# ArduinoShield.net
KiCad netlist of a schematic drawn in Altium Designer
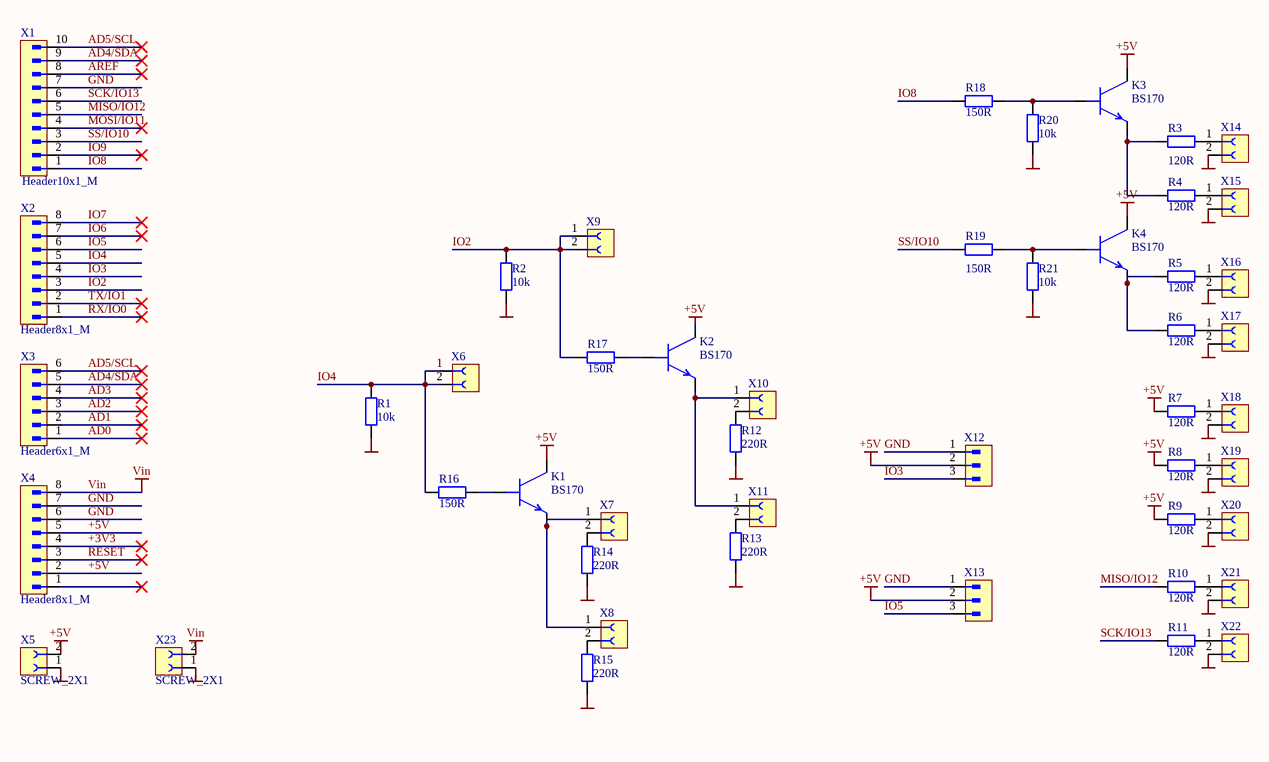
[diagram p0: ArduinoShield.SchDoc]

(export (version "E")
  (design (tool "Eeschema 10.0.6"))
  (components
    (comp (ref "K1")
      (value "BS170")
      (footprint "TO-92")
      (description "Small Signal Bipolar Transistor, 0.1A I(C), 65V V(BR)CEO, 1-Element, NPN, Silicon, TO-92")
      (fields (field (name "POWER") "625mW"))
      (libsource (lib "CPNV Centre professionnel du Nord vaudois") (part "Bipolar NPN"))
    )
    (comp (ref "K2")
      (value "BS170")
      (footprint "TO-92")
      (description "Small Signal Bipolar Transistor, 0.1A I(C), 65V V(BR)CEO, 1-Element, NPN, Silicon, TO-92")
      (fields (field (name "POWER") "625mW"))
      (libsource (lib "CPNV Centre professionnel du Nord vaudois") (part "Bipolar NPN"))
    )
    (comp (ref "K3")
      (value "BS170")
      (footprint "TO-92")
      (description "Small Signal Bipolar Transistor, 0.1A I(C), 65V V(BR)CEO, 1-Element, NPN, Silicon, TO-92")
      (fields (field (name "POWER") "625mW"))
      (libsource (lib "CPNV Centre professionnel du Nord vaudois") (part "Bipolar NPN"))
    )
    (comp (ref "K4")
      (value "BS170")
      (footprint "TO-92")
      (description "Small Signal Bipolar Transistor, 0.1A I(C), 65V V(BR)CEO, 1-Element, NPN, Silicon, TO-92")
      (fields (field (name "POWER") "625mW"))
      (libsource (lib "CPNV Centre professionnel du Nord vaudois") (part "Bipolar NPN"))
    )
    (comp (ref "R1")
      (value "10k")
      (footprint "AXIAL-1/2W")
      (description "Resistor")
      (libsource (lib "Passif_et_Semi-conducteurs") (part "RES"))
    )
    (comp (ref "R2")
      (value "10k")
      (footprint "AXIAL-1/2W")
      (description "Resistor")
      (libsource (lib "Passif_et_Semi-conducteurs") (part "RES"))
    )
    (comp (ref "R3")
      (value "120R")
      (footprint "AXIAL-1/2W")
      (description "Resistor")
      (libsource (lib "") (part "RES_1"))
    )
    (comp (ref "R4")
      (value "120R")
      (footprint "AXIAL-1/2W")
      (description "Resistor")
      (libsource (lib "") (part "RES_1"))
    )
    (comp (ref "R5")
      (value "120R")
      (footprint "AXIAL-1/2W")
      (description "Resistor")
      (libsource (lib "") (part "RES_1"))
    )
    (comp (ref "R6")
      (value "120R")
      (footprint "AXIAL-1/2W")
      (description "Resistor")
      (libsource (lib "") (part "RES_1"))
    )
    (comp (ref "R7")
      (value "120R")
      (footprint "AXIAL-1/2W")
      (description "Resistor")
      (libsource (lib "") (part "RES_1"))
    )
    (comp (ref "R8")
      (value "120R")
      (footprint "AXIAL-1/2W")
      (description "Resistor")
      (libsource (lib "") (part "RES_1"))
    )
    (comp (ref "R9")
      (value "120R")
      (footprint "AXIAL-1/2W")
      (description "Resistor")
      (libsource (lib "") (part "RES_1"))
    )
    (comp (ref "R10")
      (value "120R")
      (footprint "AXIAL-1/2W")
      (description "Resistor")
      (libsource (lib "") (part "RES_1"))
    )
    (comp (ref "R11")
      (value "120R")
      (footprint "AXIAL-1/2W")
      (description "Resistor")
      (libsource (lib "") (part "RES_1"))
    )
    (comp (ref "R12")
      (value "220R")
      (footprint "AXIAL-1/2W")
      (description "Resistor")
      (libsource (lib "Passif_et_Semi-conducteurs") (part "RES"))
    )
    (comp (ref "R13")
      (value "220R")
      (footprint "AXIAL-1/2W")
      (description "Resistor")
      (libsource (lib "Passif_et_Semi-conducteurs") (part "RES"))
    )
    (comp (ref "R14")
      (value "220R")
      (footprint "AXIAL-1/2W")
      (description "Resistor")
      (libsource (lib "Passif_et_Semi-conducteurs") (part "RES"))
    )
    (comp (ref "R15")
      (value "220R")
      (footprint "AXIAL-1/2W")
      (description "Resistor")
      (libsource (lib "Passif_et_Semi-conducteurs") (part "RES"))
    )
    (comp (ref "R16")
      (value "150R")
      (footprint "AXIAL-1/2W")
      (description "Resistor")
      (libsource (lib "") (part "RES_1"))
    )
    (comp (ref "R17")
      (value "150R")
      (footprint "AXIAL-1/2W")
      (description "Resistor")
      (libsource (lib "") (part "RES_1"))
    )
    (comp (ref "R18")
      (value "150R")
      (footprint "AXIAL-1/2W")
      (description "Resistor")
      (libsource (lib "") (part "RES_1"))
    )
    (comp (ref "R19")
      (value "150R")
      (footprint "AXIAL-1/2W")
      (description "Resistor")
      (libsource (lib "") (part "RES_1"))
    )
    (comp (ref "R20")
      (value "10k")
      (footprint "AXIAL-1/2W")
      (description "Resistor")
      (libsource (lib "Passif_et_Semi-conducteurs") (part "RES"))
    )
    (comp (ref "R21")
      (value "10k")
      (footprint "AXIAL-1/2W")
      (description "Resistor")
      (libsource (lib "Passif_et_Semi-conducteurs") (part "RES"))
    )
    (comp (ref "X1")
      (value "Header10x1_M")
      (footprint "HDR10X1_M")
      (fields
        (field (name "MANUFACTURER PART NUMBER") "61301011121")
        (field (name "MANUFACTURER") "Wurth Electronics")
        (field (name "SOURCE") "MEION_Connectors.SchLib")
      )
      (libsource (lib "CPNV Centre professionnel du Nord vaudois") (part "Header10x1_M"))
    )
    (comp (ref "X2")
      (value "Header8x1_M")
      (footprint "HDR8X1_M")
      (description "Board-To-Board Connector, Vertical, Wr-Phd Series, Through Hole, Header, 8, 2.54 Mm")
      (fields
        (field (name "MANUFACTURER") "Wurth Electronics")
        (field (name "MANUFACTURER PART NUMBER") "61300811121")
        (field (name "SOURCE") "MEION_Connectors.SchLib")
      )
      (libsource (lib "CPNV Centre professionnel du Nord vaudois") (part "Header8x1_M"))
    )
    (comp (ref "X3")
      (value "Header6x1_M")
      (footprint "HDR6X1_M")
      (fields
        (field (name "MANUFACTURER PART NUMBER") "61300611121")
        (field (name "MANUFACTURER") "Wurth Electronics")
        (field (name "SOURCE") "MEION_Connectors.SchLib")
      )
      (libsource (lib "CPNV Centre professionnel du Nord vaudois") (part "Header6x1_M"))
    )
    (comp (ref "X4")
      (value "Header8x1_M")
      (footprint "HDR8X1_M")
      (description "Board-To-Board Connector, Vertical, Wr-Phd Series, Through Hole, Header, 8, 2.54 Mm")
      (fields
        (field (name "MANUFACTURER") "Wurth Electronics")
        (field (name "MANUFACTURER PART NUMBER") "61300811121")
        (field (name "SOURCE") "MEION_Connectors.SchLib")
      )
      (libsource (lib "CPNV Centre professionnel du Nord vaudois") (part "Header8x1_M"))
    )
    (comp (ref "X5")
      (value "SCREW_2X1")
      (footprint "691210910002")
      (description "WR-TBL Serie 2109 Horizontal Entry, Rising Cage Clamp, THT, pitch 2.54mm, 2p")
      (libsource (lib "") (part "Header2x1_F_1"))
    )
    (comp (ref "X6")
      (value "SCREW_2X1")
      (footprint "691210910002")
      (description "WR-TBL Serie 2109 Horizontal Entry, Rising Cage Clamp, THT, pitch 2.54mm, 2p")
      (libsource (lib "CPNV Centre professionnel du Nord vaudois") (part "Header2x1_F"))
    )
    (comp (ref "X7")
      (value "SCREW_2X1")
      (footprint "691210910002")
      (description "WR-TBL Serie 2109 Horizontal Entry, Rising Cage Clamp, THT, pitch 2.54mm, 2p")
      (libsource (lib "CPNV Centre professionnel du Nord vaudois") (part "Header2x1_F"))
    )
    (comp (ref "X8")
      (value "SCREW_2X1")
      (footprint "691210910002")
      (description "WR-TBL Serie 2109 Horizontal Entry, Rising Cage Clamp, THT, pitch 2.54mm, 2p")
      (libsource (lib "CPNV Centre professionnel du Nord vaudois") (part "Header2x1_F"))
    )
    (comp (ref "X9")
      (value "SCREW_2X1")
      (footprint "691210910002")
      (description "WR-TBL Serie 2109 Horizontal Entry, Rising Cage Clamp, THT, pitch 2.54mm, 2p")
      (libsource (lib "CPNV Centre professionnel du Nord vaudois") (part "Header2x1_F"))
    )
    (comp (ref "X10")
      (value "SCREW_2X1")
      (footprint "691210910002")
      (description "WR-TBL Serie 2109 Horizontal Entry, Rising Cage Clamp, THT, pitch 2.54mm, 2p")
      (libsource (lib "CPNV Centre professionnel du Nord vaudois") (part "Header2x1_F"))
    )
    (comp (ref "X11")
      (value "SCREW_2X1")
      (footprint "691210910002")
      (description "WR-TBL Serie 2109 Horizontal Entry, Rising Cage Clamp, THT, pitch 2.54mm, 2p")
      (libsource (lib "CPNV Centre professionnel du Nord vaudois") (part "Header2x1_F"))
    )
    (comp (ref "X12")
      (value "Header3x1_M")
      (footprint "HDR3X1_M")
      (description "WR-PHD 2.54 mm THT Pin Header")
      (fields
        (field (name "MANUFACTURER PART NUMBER") "61300311121")
        (field (name "MANUFACTURER") "Wurth Electronics")
        (field (name "PUBLISHER") "Altium Limited")
        (field (name "SOURCE") "MEION_Connectors.SchLib")
      )
      (libsource (lib "CPNV Centre professionnel du Nord vaudois") (part "Header3x1_M"))
    )
    (comp (ref "X13")
      (value "Header3x1_M")
      (footprint "HDR3X1_M")
      (description "WR-PHD 2.54 mm THT Pin Header")
      (fields
        (field (name "MANUFACTURER PART NUMBER") "61300311121")
        (field (name "MANUFACTURER") "Wurth Electronics")
        (field (name "PUBLISHER") "Altium Limited")
        (field (name "SOURCE") "MEION_Connectors.SchLib")
      )
      (libsource (lib "CPNV Centre professionnel du Nord vaudois") (part "Header3x1_M"))
    )
    (comp (ref "X14")
      (value "SCREW_2X1")
      (footprint "691210910002")
      (description "WR-TBL Serie 2109 Horizontal Entry, Rising Cage Clamp, THT, pitch 2.54mm, 2p")
      (libsource (lib "CPNV Centre professionnel du Nord vaudois") (part "Header2x1_F"))
    )
    (comp (ref "X15")
      (value "SCREW_2X1")
      (footprint "691210910002")
      (description "WR-TBL Serie 2109 Horizontal Entry, Rising Cage Clamp, THT, pitch 2.54mm, 2p")
      (libsource (lib "CPNV Centre professionnel du Nord vaudois") (part "Header2x1_F"))
    )
    (comp (ref "X16")
      (value "SCREW_2X1")
      (footprint "691210910002")
      (description "WR-TBL Serie 2109 Horizontal Entry, Rising Cage Clamp, THT, pitch 2.54mm, 2p")
      (libsource (lib "CPNV Centre professionnel du Nord vaudois") (part "Header2x1_F"))
    )
    (comp (ref "X17")
      (value "SCREW_2X1")
      (footprint "691210910002")
      (description "WR-TBL Serie 2109 Horizontal Entry, Rising Cage Clamp, THT, pitch 2.54mm, 2p")
      (libsource (lib "CPNV Centre professionnel du Nord vaudois") (part "Header2x1_F"))
    )
    (comp (ref "X18")
      (value "SCREW_2X1")
      (footprint "691210910002")
      (description "WR-TBL Serie 2109 Horizontal Entry, Rising Cage Clamp, THT, pitch 2.54mm, 2p")
      (libsource (lib "CPNV Centre professionnel du Nord vaudois") (part "Header2x1_F"))
    )
    (comp (ref "X19")
      (value "SCREW_2X1")
      (footprint "691210910002")
      (description "WR-TBL Serie 2109 Horizontal Entry, Rising Cage Clamp, THT, pitch 2.54mm, 2p")
      (libsource (lib "CPNV Centre professionnel du Nord vaudois") (part "Header2x1_F"))
    )
    (comp (ref "X20")
      (value "SCREW_2X1")
      (footprint "691210910002")
      (description "WR-TBL Serie 2109 Horizontal Entry, Rising Cage Clamp, THT, pitch 2.54mm, 2p")
      (libsource (lib "CPNV Centre professionnel du Nord vaudois") (part "Header2x1_F"))
    )
    (comp (ref "X21")
      (value "SCREW_2X1")
      (footprint "691210910002")
      (description "WR-TBL Serie 2109 Horizontal Entry, Rising Cage Clamp, THT, pitch 2.54mm, 2p")
      (libsource (lib "CPNV Centre professionnel du Nord vaudois") (part "Header2x1_F"))
    )
    (comp (ref "X22")
      (value "SCREW_2X1")
      (footprint "691210910002")
      (description "WR-TBL Serie 2109 Horizontal Entry, Rising Cage Clamp, THT, pitch 2.54mm, 2p")
      (libsource (lib "CPNV Centre professionnel du Nord vaudois") (part "Header2x1_F"))
    )
    (comp (ref "X23")
      (value "SCREW_2X1")
      (footprint "691210910002")
      (description "WR-TBL Serie 2109 Horizontal Entry, Rising Cage Clamp, THT, pitch 2.54mm, 2p")
      (libsource (lib "") (part "Header2x1_F_1"))
    )
  )
  (nets
    (net (code "1") (name "+5V") (class "Default")
      (node (ref "K1") (pin "1") (pinfunction "C_1") (pintype "passive"))
      (node (ref "K2") (pin "1") (pinfunction "C_1") (pintype "passive"))
      (node (ref "K3") (pin "1") (pinfunction "C_1") (pintype "passive"))
      (node (ref "K4") (pin "1") (pinfunction "C_1") (pintype "passive"))
      (node (ref "R7") (pin "1") (pinfunction "1_1") (pintype "passive"))
      (node (ref "R8") (pin "1") (pinfunction "1_1") (pintype "passive"))
      (node (ref "R9") (pin "1") (pinfunction "1_1") (pintype "passive"))
      (node (ref "X12") (pin "2") (pinfunction "2_2") (pintype "passive"))
      (node (ref "X13") (pin "2") (pinfunction "2_2") (pintype "passive"))
      (node (ref "X4") (pin "2") (pinfunction "2_2") (pintype "passive"))
      (node (ref "X4") (pin "5") (pinfunction "5_5") (pintype "passive"))
      (node (ref "X5") (pin "2") (pinfunction "2_2") (pintype "passive"))
    )
    (net (code "2") (name "/+3V3") (class "Default")
      (node (ref "X4") (pin "4") (pinfunction "4_4") (pintype "passive+no_connect"))
    )
    (net (code "3") (name "/AD0") (class "Default")
      (node (ref "X3") (pin "1") (pinfunction "1_1") (pintype "passive+no_connect"))
    )
    (net (code "4") (name "/AD1") (class "Default")
      (node (ref "X3") (pin "2") (pinfunction "2_2") (pintype "passive+no_connect"))
    )
    (net (code "5") (name "/AD2") (class "Default")
      (node (ref "X3") (pin "3") (pinfunction "3_3") (pintype "passive+no_connect"))
    )
    (net (code "6") (name "/AD3") (class "Default")
      (node (ref "X3") (pin "4") (pinfunction "4_4") (pintype "passive+no_connect"))
    )
    (net (code "7") (name "/AD4{slash}SDA") (class "Default")
      (node (ref "X1") (pin "9") (pinfunction "9_9") (pintype "passive"))
      (node (ref "X3") (pin "5") (pinfunction "5_5") (pintype "passive"))
    )
    (net (code "8") (name "/AD5{slash}SCL") (class "Default")
      (node (ref "X1") (pin "10") (pinfunction "10_10") (pintype "passive"))
      (node (ref "X3") (pin "6") (pinfunction "6_6") (pintype "passive"))
    )
    (net (code "9") (name "/AREF") (class "Default")
      (node (ref "X1") (pin "8") (pinfunction "8_8") (pintype "passive+no_connect"))
    )
    (net (code "10") (name "/IO2") (class "Default")
      (node (ref "R17") (pin "1") (pinfunction "1_1") (pintype "passive"))
      (node (ref "R2") (pin "1") (pinfunction "1_1") (pintype "passive"))
      (node (ref "X2") (pin "3") (pinfunction "3_3") (pintype "passive"))
      (node (ref "X9") (pin "1") (pinfunction "1_1") (pintype "passive"))
      (node (ref "X9") (pin "2") (pinfunction "2_2") (pintype "passive"))
    )
    (net (code "11") (name "/IO3") (class "Default")
      (node (ref "X12") (pin "3") (pinfunction "3_3") (pintype "passive"))
      (node (ref "X2") (pin "4") (pinfunction "4_4") (pintype "passive"))
    )
    (net (code "12") (name "/IO4") (class "Default")
      (node (ref "R1") (pin "1") (pinfunction "1_1") (pintype "passive"))
      (node (ref "R16") (pin "1") (pinfunction "1_1") (pintype "passive"))
      (node (ref "X2") (pin "5") (pinfunction "5_5") (pintype "passive"))
      (node (ref "X6") (pin "1") (pinfunction "1_1") (pintype "passive"))
      (node (ref "X6") (pin "2") (pinfunction "2_2") (pintype "passive"))
    )
    (net (code "13") (name "/IO5") (class "Default")
      (node (ref "X13") (pin "3") (pinfunction "3_3") (pintype "passive"))
      (node (ref "X2") (pin "6") (pinfunction "6_6") (pintype "passive"))
    )
    (net (code "14") (name "/IO6") (class "Default")
      (node (ref "X2") (pin "7") (pinfunction "7_7") (pintype "passive+no_connect"))
    )
    (net (code "15") (name "/IO7") (class "Default")
      (node (ref "X2") (pin "8") (pinfunction "8_8") (pintype "passive+no_connect"))
    )
    (net (code "16") (name "/IO8") (class "Default")
      (node (ref "R18") (pin "1") (pinfunction "1_1") (pintype "passive"))
      (node (ref "X1") (pin "1") (pinfunction "1_1") (pintype "passive"))
    )
    (net (code "17") (name "/IO9") (class "Default")
      (node (ref "X1") (pin "2") (pinfunction "2_2") (pintype "passive+no_connect"))
    )
    (net (code "18") (name "/MISO{slash}IO12") (class "Default")
      (node (ref "R10") (pin "1") (pinfunction "1_1") (pintype "passive"))
      (node (ref "X1") (pin "5") (pinfunction "5_5") (pintype "passive"))
    )
    (net (code "19") (name "/MOSI{slash}IO11") (class "Default")
      (node (ref "X1") (pin "4") (pinfunction "4_4") (pintype "passive+no_connect"))
    )
    (net (code "20") (name "/RESET") (class "Default")
      (node (ref "X4") (pin "3") (pinfunction "3_3") (pintype "passive+no_connect"))
    )
    (net (code "21") (name "/RX{slash}IO0") (class "Default")
      (node (ref "X2") (pin "1") (pinfunction "1_1") (pintype "passive+no_connect"))
    )
    (net (code "22") (name "/SCK{slash}IO13") (class "Default")
      (node (ref "R11") (pin "1") (pinfunction "1_1") (pintype "passive"))
      (node (ref "X1") (pin "6") (pinfunction "6_6") (pintype "passive"))
    )
    (net (code "23") (name "/SS{slash}IO10") (class "Default")
      (node (ref "R19") (pin "1") (pinfunction "1_1") (pintype "passive"))
      (node (ref "X1") (pin "3") (pinfunction "3_3") (pintype "passive"))
    )
    (net (code "24") (name "/TX{slash}IO1") (class "Default")
      (node (ref "X2") (pin "2") (pinfunction "2_2") (pintype "passive+no_connect"))
    )
    (net (code "25") (name "GND") (class "Default")
      (node (ref "R1") (pin "2") (pinfunction "2_2") (pintype "passive"))
      (node (ref "R12") (pin "2") (pinfunction "2_2") (pintype "passive"))
      (node (ref "R13") (pin "2") (pinfunction "2_2") (pintype "passive"))
      (node (ref "R14") (pin "2") (pinfunction "2_2") (pintype "passive"))
      (node (ref "R15") (pin "2") (pinfunction "2_2") (pintype "passive"))
      (node (ref "R2") (pin "2") (pinfunction "2_2") (pintype "passive"))
      (node (ref "R20") (pin "2") (pinfunction "2_2") (pintype "passive"))
      (node (ref "R21") (pin "2") (pinfunction "2_2") (pintype "passive"))
      (node (ref "X1") (pin "7") (pinfunction "7_7") (pintype "passive"))
      (node (ref "X12") (pin "1") (pinfunction "1_1") (pintype "passive"))
      (node (ref "X13") (pin "1") (pinfunction "1_1") (pintype "passive"))
      (node (ref "X14") (pin "2") (pinfunction "2_2") (pintype "passive"))
      (node (ref "X15") (pin "2") (pinfunction "2_2") (pintype "passive"))
      (node (ref "X16") (pin "2") (pinfunction "2_2") (pintype "passive"))
      (node (ref "X17") (pin "2") (pinfunction "2_2") (pintype "passive"))
      (node (ref "X18") (pin "2") (pinfunction "2_2") (pintype "passive"))
      (node (ref "X19") (pin "2") (pinfunction "2_2") (pintype "passive"))
      (node (ref "X20") (pin "2") (pinfunction "2_2") (pintype "passive"))
      (node (ref "X21") (pin "2") (pinfunction "2_2") (pintype "passive"))
      (node (ref "X22") (pin "2") (pinfunction "2_2") (pintype "passive"))
      (node (ref "X23") (pin "1") (pinfunction "1_1") (pintype "passive"))
      (node (ref "X4") (pin "6") (pinfunction "6_6") (pintype "passive"))
      (node (ref "X4") (pin "7") (pinfunction "7_7") (pintype "passive"))
      (node (ref "X5") (pin "1") (pinfunction "1_1") (pintype "passive"))
    )
    (net (code "26") (name "Net-(K1-B)") (class "Default")
      (node (ref "K1") (pin "2") (pinfunction "B_2") (pintype "passive"))
      (node (ref "R16") (pin "2") (pinfunction "2_2") (pintype "passive"))
    )
    (net (code "27") (name "Net-(K1-E)") (class "Default")
      (node (ref "K1") (pin "3") (pinfunction "E_3") (pintype "passive"))
      (node (ref "X7") (pin "1") (pinfunction "1_1") (pintype "passive"))
      (node (ref "X8") (pin "1") (pinfunction "1_1") (pintype "passive"))
    )
    (net (code "28") (name "Net-(K2-B)") (class "Default")
      (node (ref "K2") (pin "2") (pinfunction "B_2") (pintype "passive"))
      (node (ref "R17") (pin "2") (pinfunction "2_2") (pintype "passive"))
    )
    (net (code "29") (name "Net-(K2-E)") (class "Default")
      (node (ref "K2") (pin "3") (pinfunction "E_3") (pintype "passive"))
      (node (ref "X10") (pin "1") (pinfunction "1_1") (pintype "passive"))
      (node (ref "X11") (pin "1") (pinfunction "1_1") (pintype "passive"))
    )
    (net (code "30") (name "Net-(K3-B)") (class "Default")
      (node (ref "K3") (pin "2") (pinfunction "B_2") (pintype "passive"))
      (node (ref "R18") (pin "2") (pinfunction "2_2") (pintype "passive"))
      (node (ref "R20") (pin "1") (pinfunction "1_1") (pintype "passive"))
    )
    (net (code "31") (name "Net-(K3-E)") (class "Default")
      (node (ref "K3") (pin "3") (pinfunction "E_3") (pintype "passive"))
      (node (ref "R3") (pin "1") (pinfunction "1_1") (pintype "passive"))
      (node (ref "R4") (pin "1") (pinfunction "1_1") (pintype "passive"))
    )
    (net (code "32") (name "Net-(K4-B)") (class "Default")
      (node (ref "K4") (pin "2") (pinfunction "B_2") (pintype "passive"))
      (node (ref "R19") (pin "2") (pinfunction "2_2") (pintype "passive"))
      (node (ref "R21") (pin "1") (pinfunction "1_1") (pintype "passive"))
    )
    (net (code "33") (name "Net-(K4-E)") (class "Default")
      (node (ref "K4") (pin "3") (pinfunction "E_3") (pintype "passive"))
      (node (ref "R5") (pin "1") (pinfunction "1_1") (pintype "passive"))
      (node (ref "R6") (pin "1") (pinfunction "1_1") (pintype "passive"))
    )
    (net (code "34") (name "Net-(R3-Pad2)") (class "Default")
      (node (ref "R3") (pin "2") (pinfunction "2_2") (pintype "passive"))
      (node (ref "X14") (pin "1") (pinfunction "1_1") (pintype "passive"))
    )
    (net (code "35") (name "Net-(R4-Pad2)") (class "Default")
      (node (ref "R4") (pin "2") (pinfunction "2_2") (pintype "passive"))
      (node (ref "X15") (pin "1") (pinfunction "1_1") (pintype "passive"))
    )
    (net (code "36") (name "Net-(R5-Pad2)") (class "Default")
      (node (ref "R5") (pin "2") (pinfunction "2_2") (pintype "passive"))
      (node (ref "X16") (pin "1") (pinfunction "1_1") (pintype "passive"))
    )
    (net (code "37") (name "Net-(R6-Pad2)") (class "Default")
      (node (ref "R6") (pin "2") (pinfunction "2_2") (pintype "passive"))
      (node (ref "X17") (pin "1") (pinfunction "1_1") (pintype "passive"))
    )
    (net (code "38") (name "Net-(R7-Pad2)") (class "Default")
      (node (ref "R7") (pin "2") (pinfunction "2_2") (pintype "passive"))
      (node (ref "X18") (pin "1") (pinfunction "1_1") (pintype "passive"))
    )
    (net (code "39") (name "Net-(R8-Pad2)") (class "Default")
      (node (ref "R8") (pin "2") (pinfunction "2_2") (pintype "passive"))
      (node (ref "X19") (pin "1") (pinfunction "1_1") (pintype "passive"))
    )
    (net (code "40") (name "Net-(R9-Pad2)") (class "Default")
      (node (ref "R9") (pin "2") (pinfunction "2_2") (pintype "passive"))
      (node (ref "X20") (pin "1") (pinfunction "1_1") (pintype "passive"))
    )
    (net (code "41") (name "Net-(R10-Pad2)") (class "Default")
      (node (ref "R10") (pin "2") (pinfunction "2_2") (pintype "passive"))
      (node (ref "X21") (pin "1") (pinfunction "1_1") (pintype "passive"))
    )
    (net (code "42") (name "Net-(R11-Pad2)") (class "Default")
      (node (ref "R11") (pin "2") (pinfunction "2_2") (pintype "passive"))
      (node (ref "X22") (pin "1") (pinfunction "1_1") (pintype "passive"))
    )
    (net (code "43") (name "Net-(R12-Pad1)") (class "Default")
      (node (ref "R12") (pin "1") (pinfunction "1_1") (pintype "passive"))
      (node (ref "X10") (pin "2") (pinfunction "2_2") (pintype "passive"))
    )
    (net (code "44") (name "Net-(R13-Pad1)") (class "Default")
      (node (ref "R13") (pin "1") (pinfunction "1_1") (pintype "passive"))
      (node (ref "X11") (pin "2") (pinfunction "2_2") (pintype "passive"))
    )
    (net (code "45") (name "Net-(R14-Pad1)") (class "Default")
      (node (ref "R14") (pin "1") (pinfunction "1_1") (pintype "passive"))
      (node (ref "X7") (pin "2") (pinfunction "2_2") (pintype "passive"))
    )
    (net (code "46") (name "Net-(R15-Pad1)") (class "Default")
      (node (ref "R15") (pin "1") (pinfunction "1_1") (pintype "passive"))
      (node (ref "X8") (pin "2") (pinfunction "2_2") (pintype "passive"))
    )
    (net (code "47") (name "Vin") (class "Default")
      (node (ref "X23") (pin "2") (pinfunction "2_2") (pintype "passive"))
      (node (ref "X4") (pin "8") (pinfunction "8_8") (pintype "passive"))
    )
    (net (code "48") (name "unconnected-(X4-Pad1)") (class "Default")
      (node (ref "X4") (pin "1") (pinfunction "1_1") (pintype "passive+no_connect"))
    )
  )
)
